# Pots.net
KiCad netlist of a schematic drawn in EAGLE
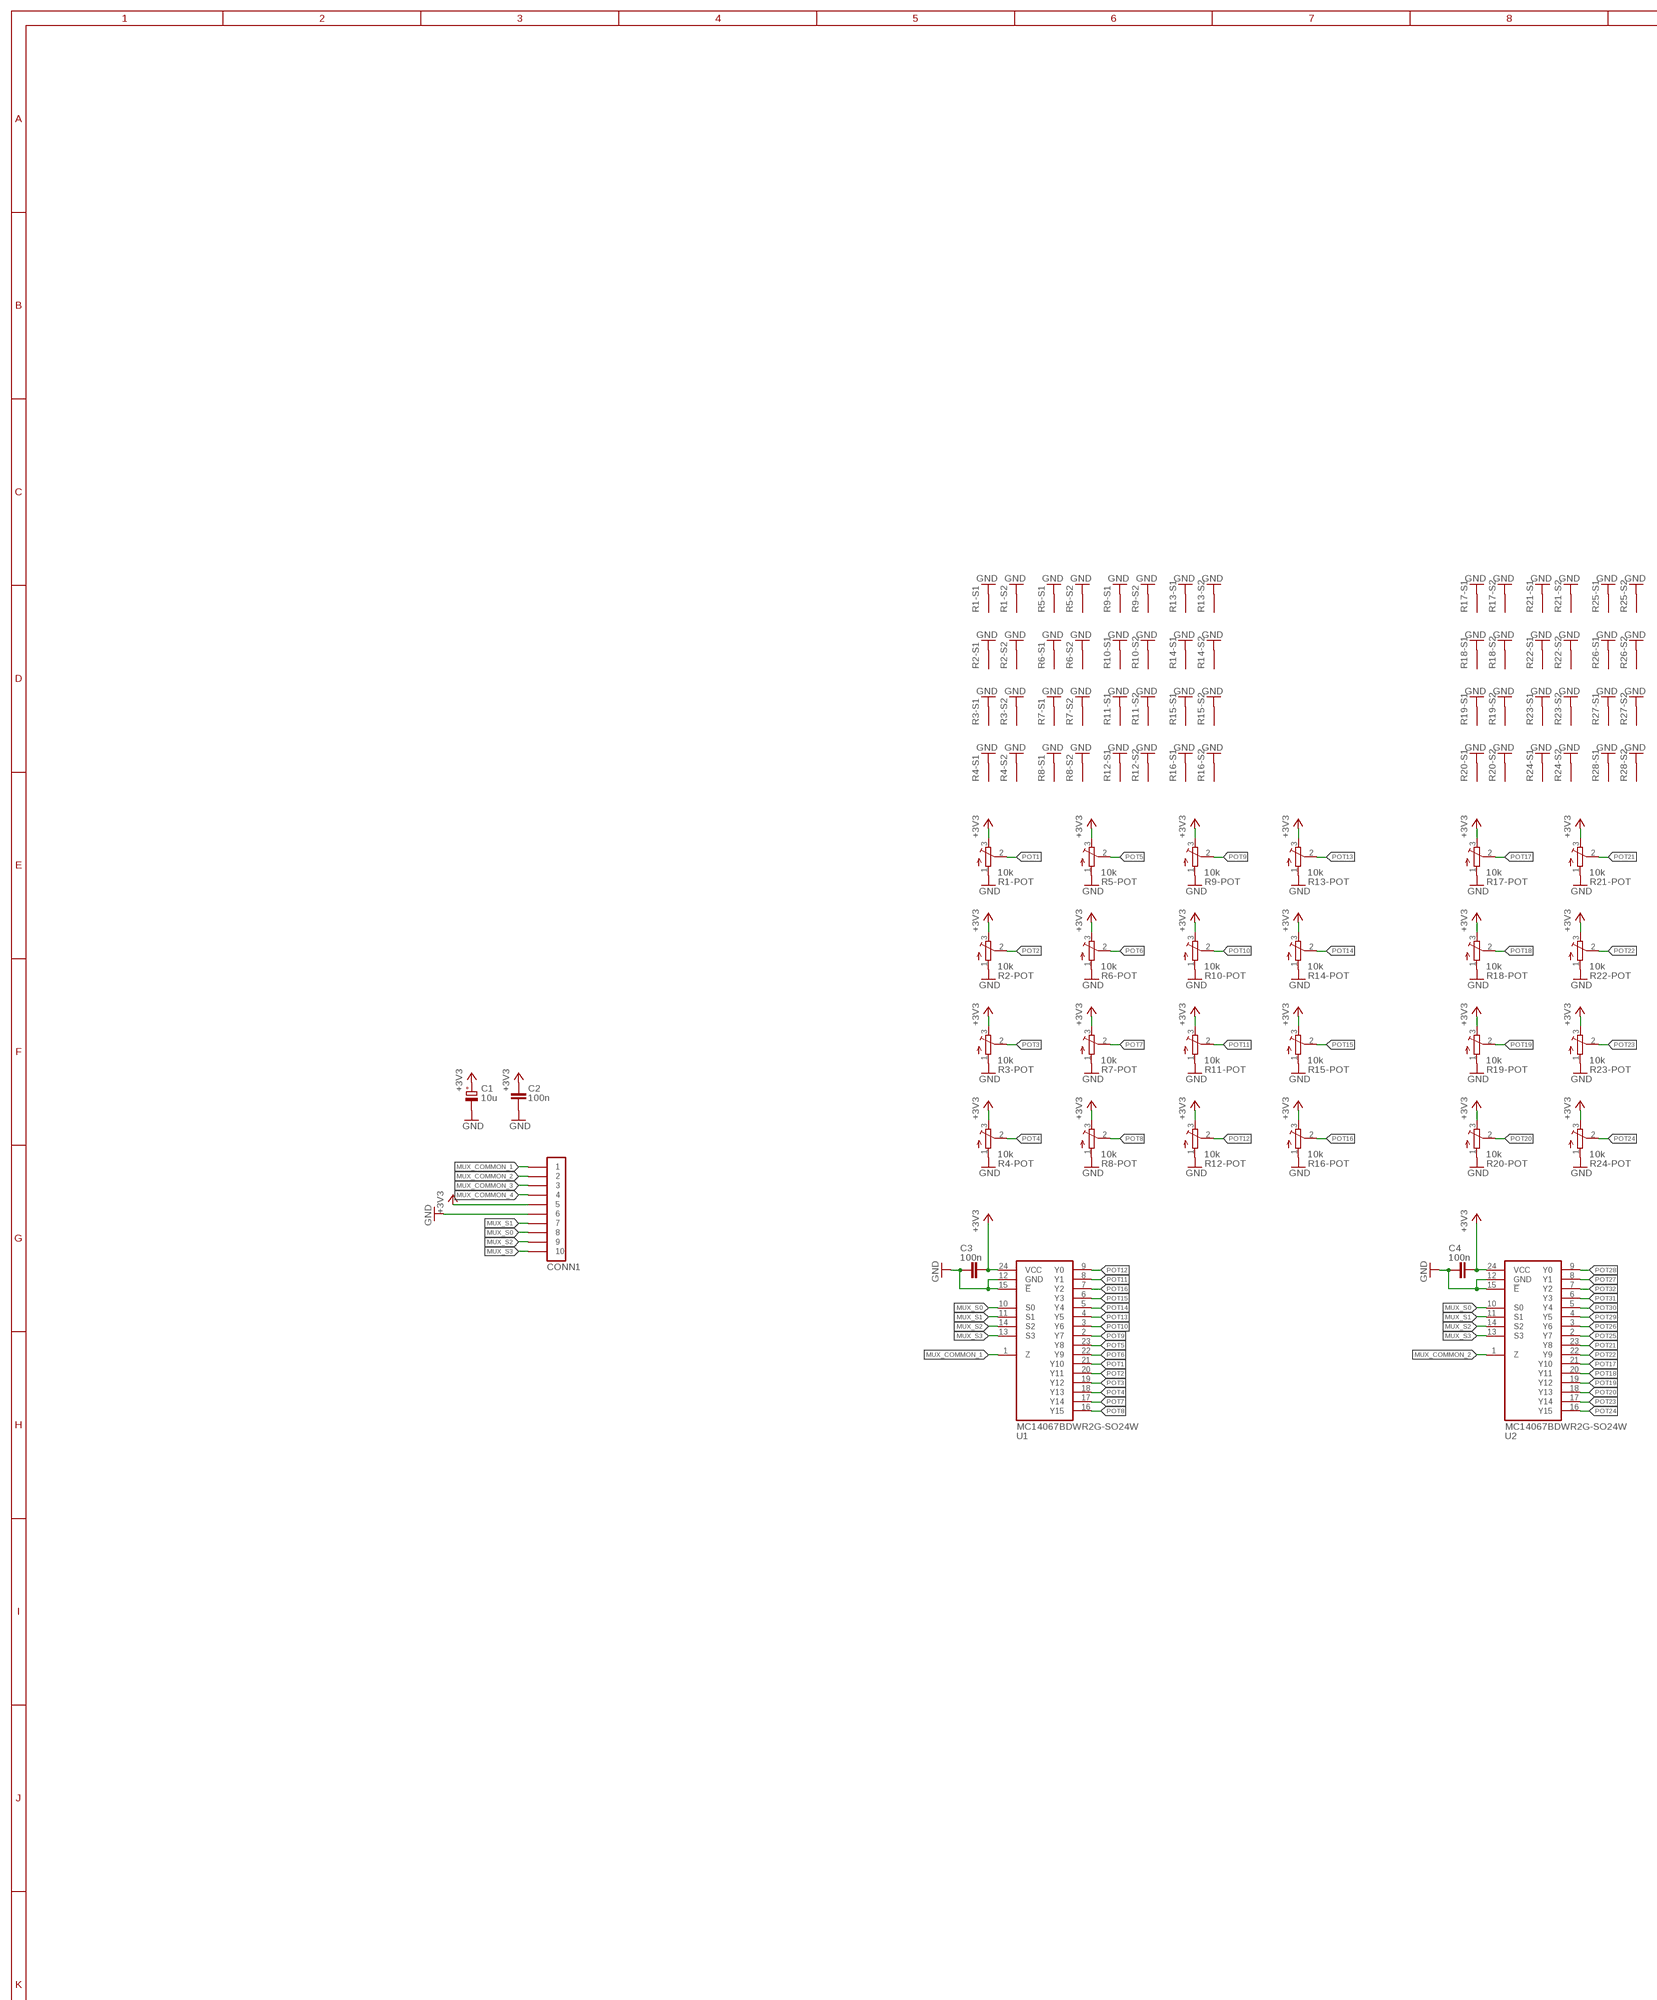
[diagram p0: schematic, sheet 1, part 1 of 3]
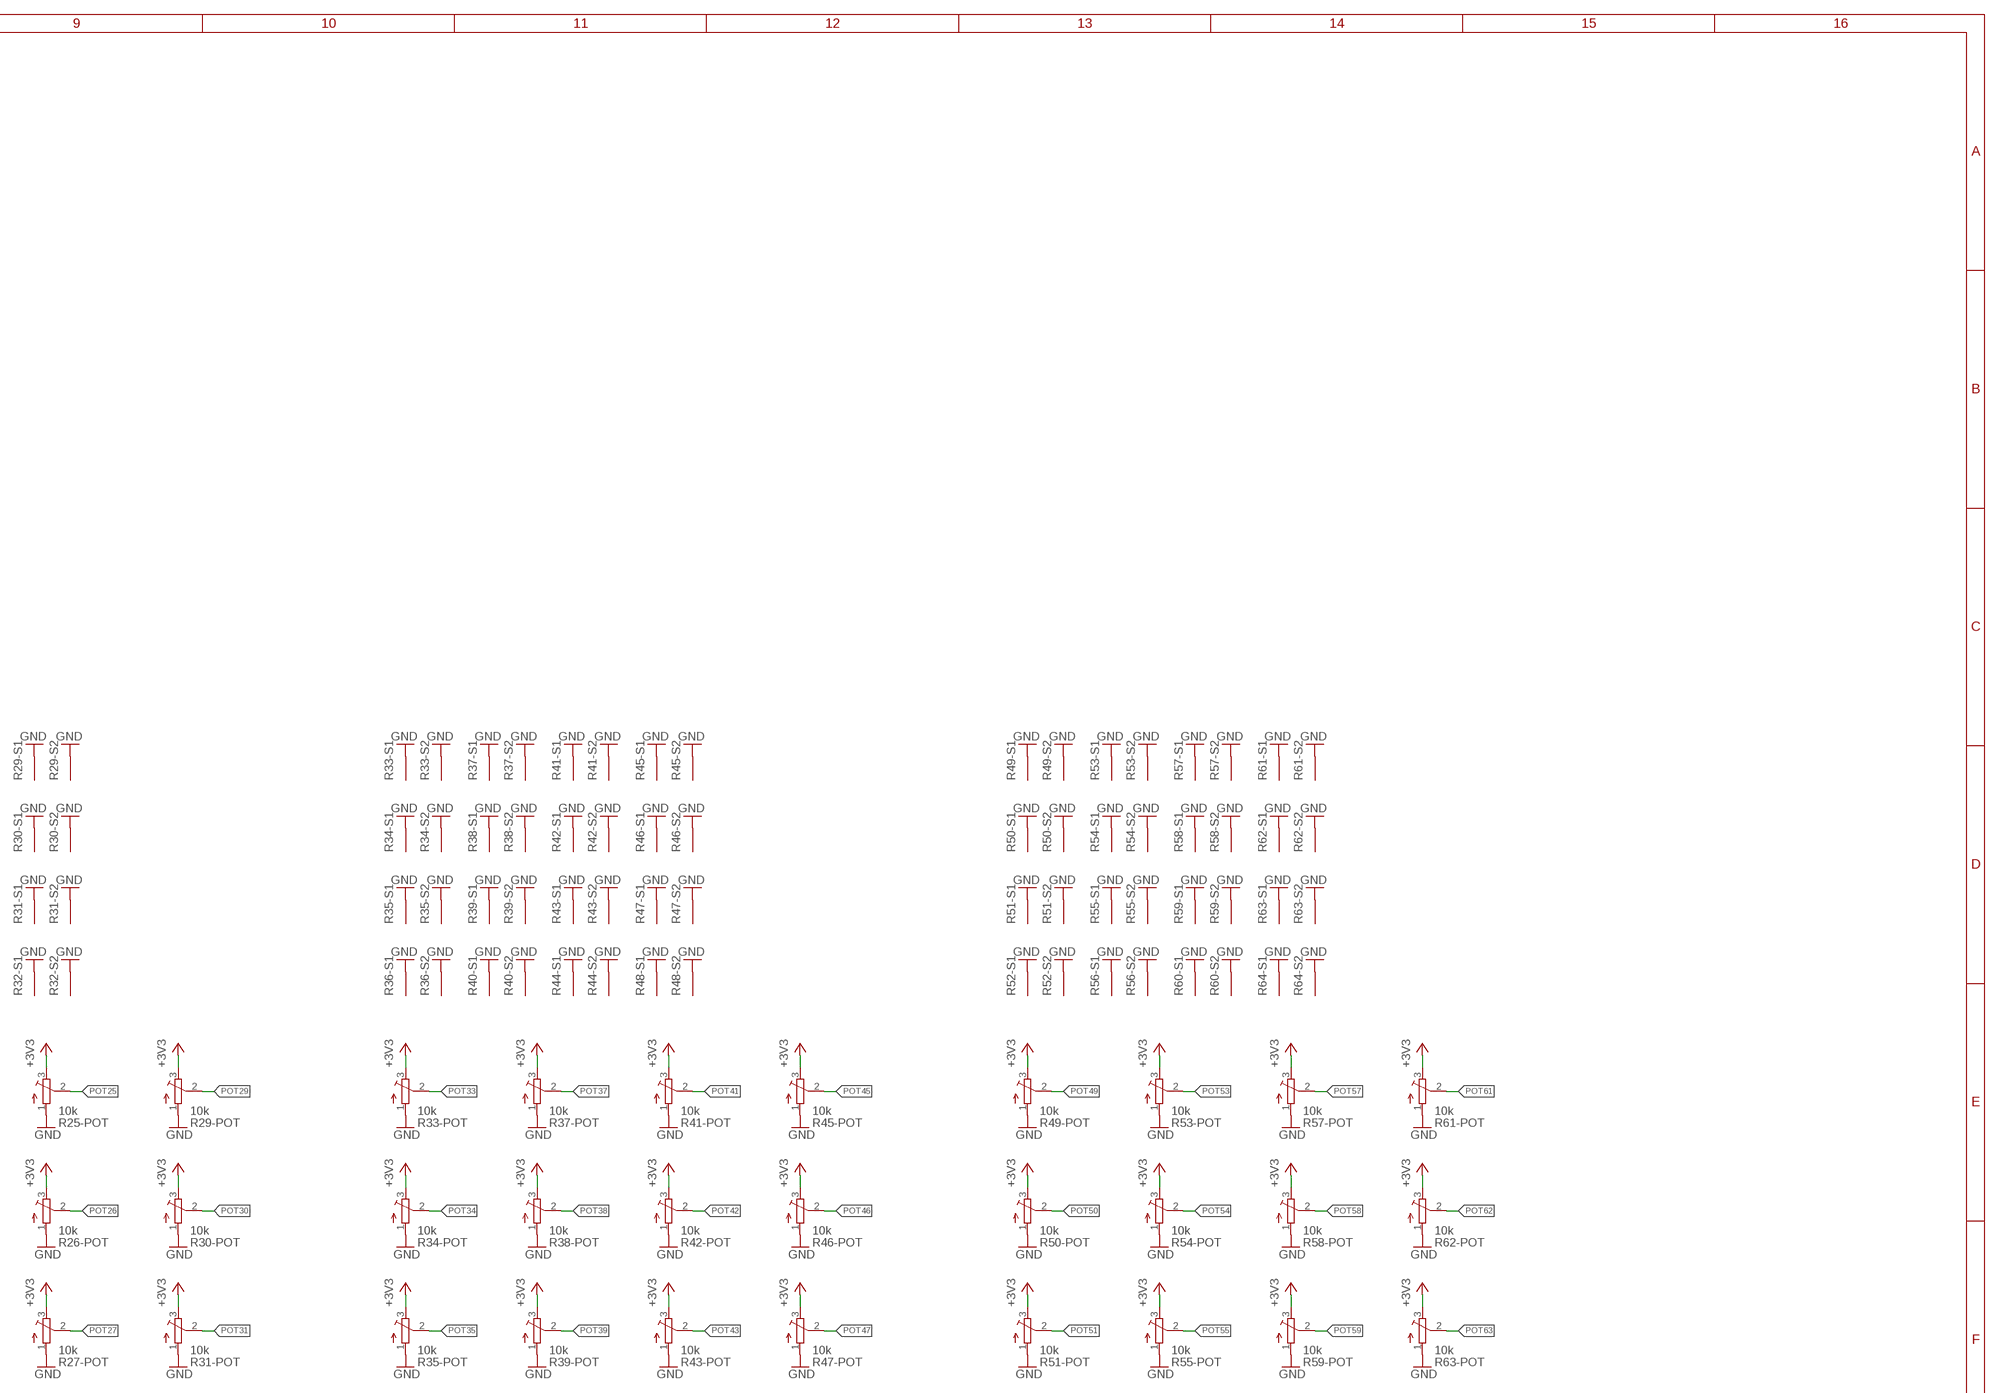
[diagram p1: schematic, sheet 1, part 2 of 3]
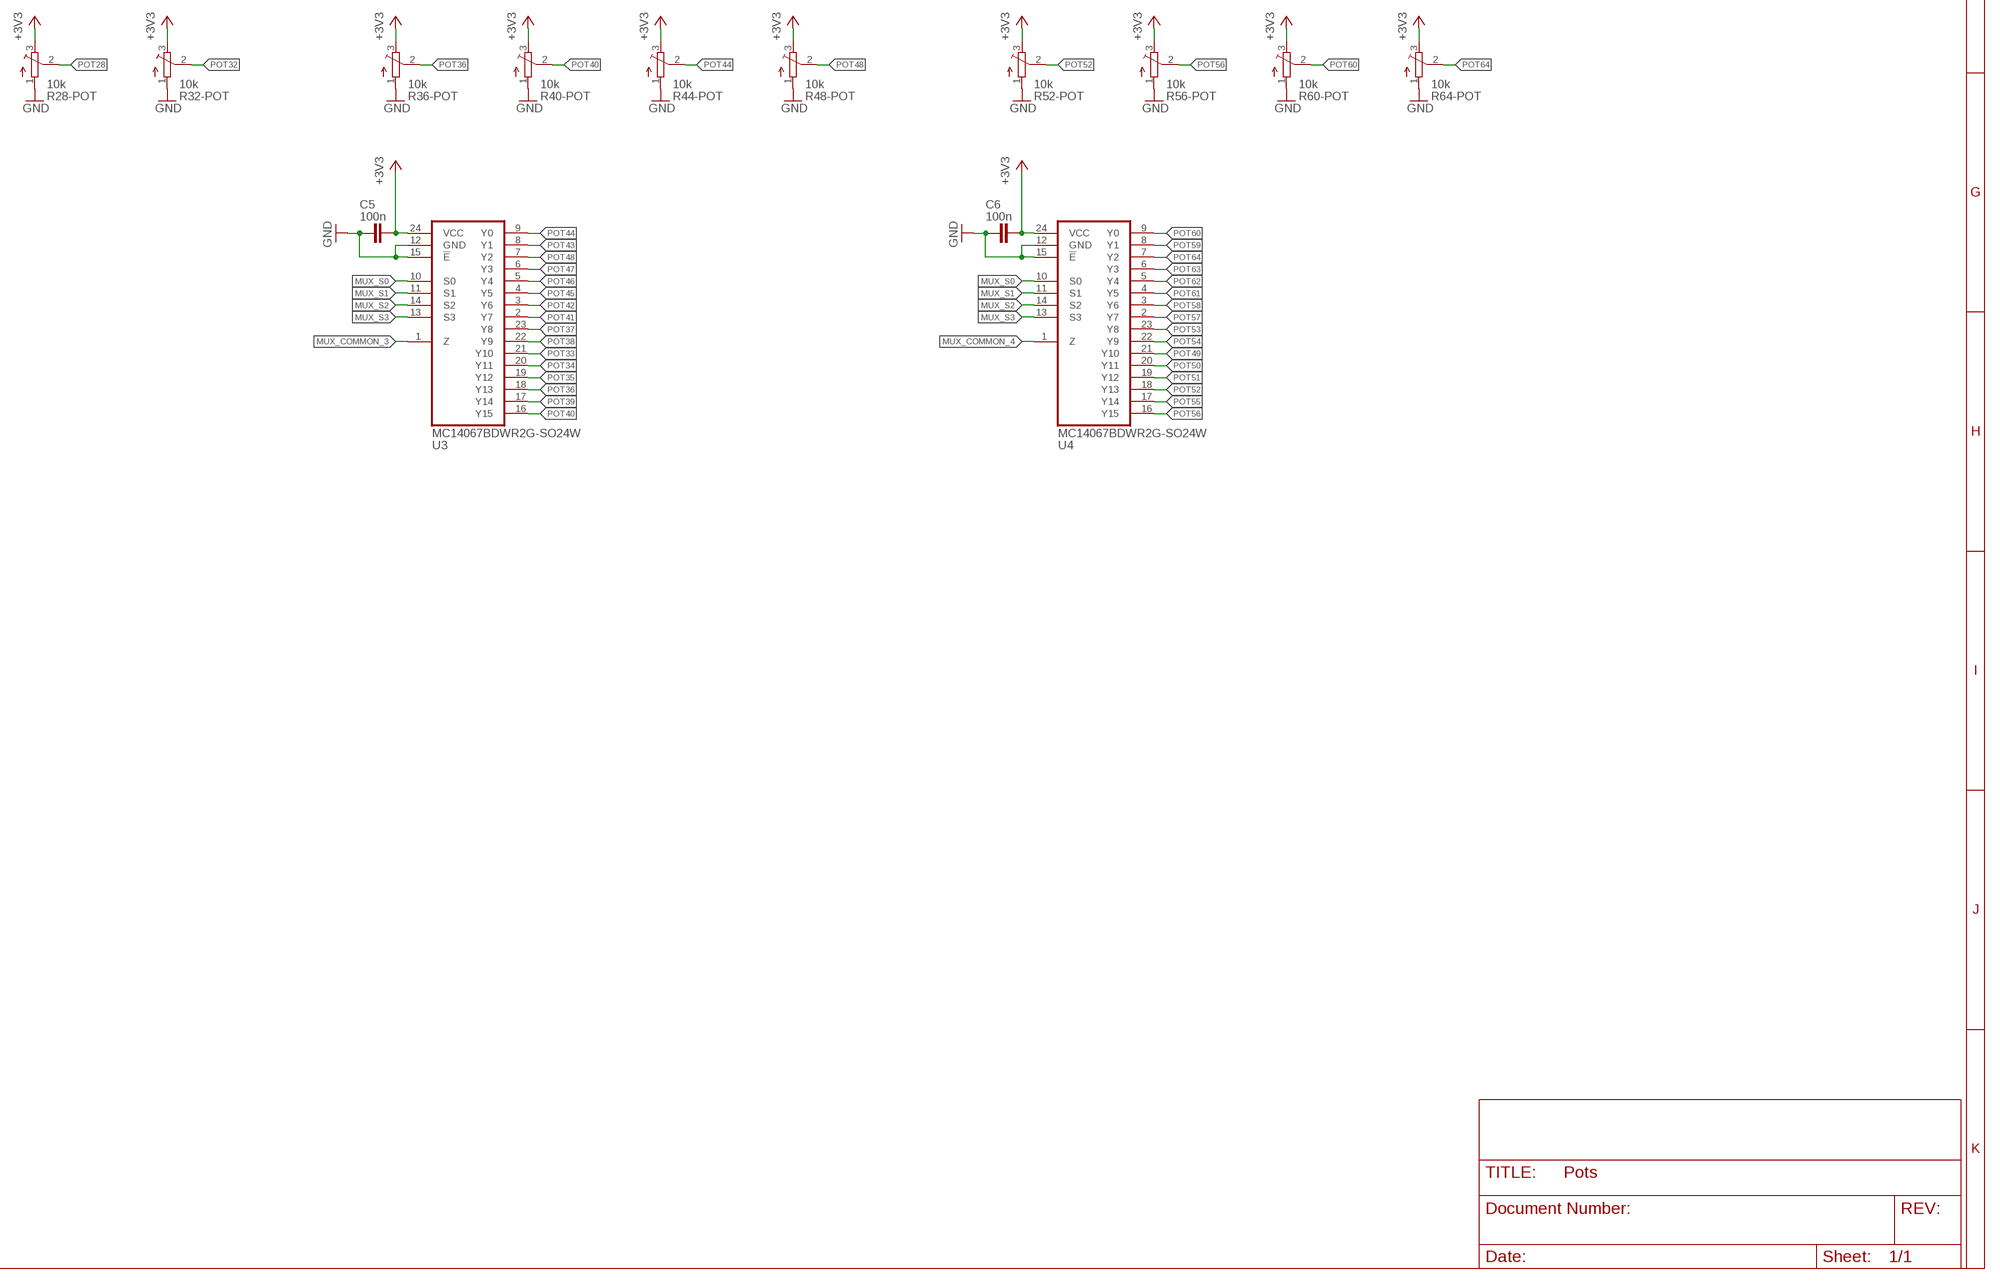
[diagram p2: schematic, sheet 1, part 3 of 3]

(export (version "E")
  (design (tool "Eeschema 10.0.6"))
  (components
    (comp (ref "C1")
      (value "10u")
      (footprint "eagle-import:C-TH-E-0401")
      (libsource (lib "eagle-import") (part "ELECTROLYTIC_CAPACITOR-C-TH-E-0401"))
    )
    (comp (ref "C2")
      (value "100n")
      (footprint "eagle-import:C0805")
      (libsource (lib "eagle-import") (part "CAPACITOR-0805"))
    )
    (comp (ref "C3")
      (value "100n")
      (footprint "eagle-import:C0805")
      (libsource (lib "eagle-import") (part "CAPACITOR-0805"))
    )
    (comp (ref "C4")
      (value "100n")
      (footprint "eagle-import:C0805")
      (libsource (lib "eagle-import") (part "CAPACITOR-0805"))
    )
    (comp (ref "C5")
      (value "100n")
      (footprint "eagle-import:C0805")
      (libsource (lib "eagle-import") (part "CAPACITOR-0805"))
    )
    (comp (ref "C6")
      (value "100n")
      (footprint "eagle-import:C0805")
      (libsource (lib "eagle-import") (part "CAPACITOR-0805"))
    )
    (comp (ref "CONN1")
      (value "PINHD-1X10-FFC-1MM-Z")
      (footprint "eagle-import:MOLEX-52271-1079")
      (fields (field (name "MANUFACTURER") "Molex") (field (name "MPN") "52271-1079"))
      (libsource (lib "eagle-import") (part "PINHD-1X10-FFC-1MM-Z"))
    )
    (comp (ref "R1")
      (value "10k")
      (footprint "eagle-import:PTV09A-4025F-B103")
      (libsource (lib "eagle-import") (part "PTV09A-4025F-B103"))
    )
    (comp (ref "R2")
      (value "10k")
      (footprint "eagle-import:PTV09A-4025F-B103")
      (libsource (lib "eagle-import") (part "PTV09A-4025F-B103"))
    )
    (comp (ref "R3")
      (value "10k")
      (footprint "eagle-import:PTV09A-4025F-B103")
      (libsource (lib "eagle-import") (part "PTV09A-4025F-B103"))
    )
    (comp (ref "R4")
      (value "10k")
      (footprint "eagle-import:PTV09A-4025F-B103")
      (libsource (lib "eagle-import") (part "PTV09A-4025F-B103"))
    )
    (comp (ref "R5")
      (value "10k")
      (footprint "eagle-import:PTV09A-4025F-B103")
      (libsource (lib "eagle-import") (part "PTV09A-4025F-B103"))
    )
    (comp (ref "R6")
      (value "10k")
      (footprint "eagle-import:PTV09A-4025F-B103")
      (libsource (lib "eagle-import") (part "PTV09A-4025F-B103"))
    )
    (comp (ref "R7")
      (value "10k")
      (footprint "eagle-import:PTV09A-4025F-B103")
      (libsource (lib "eagle-import") (part "PTV09A-4025F-B103"))
    )
    (comp (ref "R8")
      (value "10k")
      (footprint "eagle-import:PTV09A-4025F-B103")
      (libsource (lib "eagle-import") (part "PTV09A-4025F-B103"))
    )
    (comp (ref "R9")
      (value "10k")
      (footprint "eagle-import:PTV09A-4025F-B103")
      (libsource (lib "eagle-import") (part "PTV09A-4025F-B103"))
    )
    (comp (ref "R10")
      (value "10k")
      (footprint "eagle-import:PTV09A-4025F-B103")
      (libsource (lib "eagle-import") (part "PTV09A-4025F-B103"))
    )
    (comp (ref "R11")
      (value "10k")
      (footprint "eagle-import:PTV09A-4025F-B103")
      (libsource (lib "eagle-import") (part "PTV09A-4025F-B103"))
    )
    (comp (ref "R12")
      (value "10k")
      (footprint "eagle-import:PTV09A-4025F-B103")
      (libsource (lib "eagle-import") (part "PTV09A-4025F-B103"))
    )
    (comp (ref "R13")
      (value "10k")
      (footprint "eagle-import:PTV09A-4025F-B103")
      (libsource (lib "eagle-import") (part "PTV09A-4025F-B103"))
    )
    (comp (ref "R14")
      (value "10k")
      (footprint "eagle-import:PTV09A-4025F-B103")
      (libsource (lib "eagle-import") (part "PTV09A-4025F-B103"))
    )
    (comp (ref "R15")
      (value "10k")
      (footprint "eagle-import:PTV09A-4025F-B103")
      (libsource (lib "eagle-import") (part "PTV09A-4025F-B103"))
    )
    (comp (ref "R16")
      (value "10k")
      (footprint "eagle-import:PTV09A-4025F-B103")
      (libsource (lib "eagle-import") (part "PTV09A-4025F-B103"))
    )
    (comp (ref "R17")
      (value "10k")
      (footprint "eagle-import:PTV09A-4025F-B103")
      (libsource (lib "eagle-import") (part "PTV09A-4025F-B103"))
    )
    (comp (ref "R18")
      (value "10k")
      (footprint "eagle-import:PTV09A-4025F-B103")
      (libsource (lib "eagle-import") (part "PTV09A-4025F-B103"))
    )
    (comp (ref "R19")
      (value "10k")
      (footprint "eagle-import:PTV09A-4025F-B103")
      (libsource (lib "eagle-import") (part "PTV09A-4025F-B103"))
    )
    (comp (ref "R20")
      (value "10k")
      (footprint "eagle-import:PTV09A-4025F-B103")
      (libsource (lib "eagle-import") (part "PTV09A-4025F-B103"))
    )
    (comp (ref "R21")
      (value "10k")
      (footprint "eagle-import:PTV09A-4025F-B103")
      (libsource (lib "eagle-import") (part "PTV09A-4025F-B103"))
    )
    (comp (ref "R22")
      (value "10k")
      (footprint "eagle-import:PTV09A-4025F-B103")
      (libsource (lib "eagle-import") (part "PTV09A-4025F-B103"))
    )
    (comp (ref "R23")
      (value "10k")
      (footprint "eagle-import:PTV09A-4025F-B103")
      (libsource (lib "eagle-import") (part "PTV09A-4025F-B103"))
    )
    (comp (ref "R24")
      (value "10k")
      (footprint "eagle-import:PTV09A-4025F-B103")
      (libsource (lib "eagle-import") (part "PTV09A-4025F-B103"))
    )
    (comp (ref "R25")
      (value "10k")
      (footprint "eagle-import:PTV09A-4025F-B103")
      (libsource (lib "eagle-import") (part "PTV09A-4025F-B103"))
    )
    (comp (ref "R26")
      (value "10k")
      (footprint "eagle-import:PTV09A-4025F-B103")
      (libsource (lib "eagle-import") (part "PTV09A-4025F-B103"))
    )
    (comp (ref "R27")
      (value "10k")
      (footprint "eagle-import:PTV09A-4025F-B103")
      (libsource (lib "eagle-import") (part "PTV09A-4025F-B103"))
    )
    (comp (ref "R28")
      (value "10k")
      (footprint "eagle-import:PTV09A-4025F-B103")
      (libsource (lib "eagle-import") (part "PTV09A-4025F-B103"))
    )
    (comp (ref "R29")
      (value "10k")
      (footprint "eagle-import:PTV09A-4025F-B103")
      (libsource (lib "eagle-import") (part "PTV09A-4025F-B103"))
    )
    (comp (ref "R30")
      (value "10k")
      (footprint "eagle-import:PTV09A-4025F-B103")
      (libsource (lib "eagle-import") (part "PTV09A-4025F-B103"))
    )
    (comp (ref "R31")
      (value "10k")
      (footprint "eagle-import:PTV09A-4025F-B103")
      (libsource (lib "eagle-import") (part "PTV09A-4025F-B103"))
    )
    (comp (ref "R32")
      (value "10k")
      (footprint "eagle-import:PTV09A-4025F-B103")
      (libsource (lib "eagle-import") (part "PTV09A-4025F-B103"))
    )
    (comp (ref "R33")
      (value "10k")
      (footprint "eagle-import:PTV09A-4025F-B103")
      (libsource (lib "eagle-import") (part "PTV09A-4025F-B103"))
    )
    (comp (ref "R34")
      (value "10k")
      (footprint "eagle-import:PTV09A-4025F-B103")
      (libsource (lib "eagle-import") (part "PTV09A-4025F-B103"))
    )
    (comp (ref "R35")
      (value "10k")
      (footprint "eagle-import:PTV09A-4025F-B103")
      (libsource (lib "eagle-import") (part "PTV09A-4025F-B103"))
    )
    (comp (ref "R36")
      (value "10k")
      (footprint "eagle-import:PTV09A-4025F-B103")
      (libsource (lib "eagle-import") (part "PTV09A-4025F-B103"))
    )
    (comp (ref "R37")
      (value "10k")
      (footprint "eagle-import:PTV09A-4025F-B103")
      (libsource (lib "eagle-import") (part "PTV09A-4025F-B103"))
    )
    (comp (ref "R38")
      (value "10k")
      (footprint "eagle-import:PTV09A-4025F-B103")
      (libsource (lib "eagle-import") (part "PTV09A-4025F-B103"))
    )
    (comp (ref "R39")
      (value "10k")
      (footprint "eagle-import:PTV09A-4025F-B103")
      (libsource (lib "eagle-import") (part "PTV09A-4025F-B103"))
    )
    (comp (ref "R40")
      (value "10k")
      (footprint "eagle-import:PTV09A-4025F-B103")
      (libsource (lib "eagle-import") (part "PTV09A-4025F-B103"))
    )
    (comp (ref "R41")
      (value "10k")
      (footprint "eagle-import:PTV09A-4025F-B103")
      (libsource (lib "eagle-import") (part "PTV09A-4025F-B103"))
    )
    (comp (ref "R42")
      (value "10k")
      (footprint "eagle-import:PTV09A-4025F-B103")
      (libsource (lib "eagle-import") (part "PTV09A-4025F-B103"))
    )
    (comp (ref "R43")
      (value "10k")
      (footprint "eagle-import:PTV09A-4025F-B103")
      (libsource (lib "eagle-import") (part "PTV09A-4025F-B103"))
    )
    (comp (ref "R44")
      (value "10k")
      (footprint "eagle-import:PTV09A-4025F-B103")
      (libsource (lib "eagle-import") (part "PTV09A-4025F-B103"))
    )
    (comp (ref "R45")
      (value "10k")
      (footprint "eagle-import:PTV09A-4025F-B103")
      (libsource (lib "eagle-import") (part "PTV09A-4025F-B103"))
    )
    (comp (ref "R46")
      (value "10k")
      (footprint "eagle-import:PTV09A-4025F-B103")
      (libsource (lib "eagle-import") (part "PTV09A-4025F-B103"))
    )
    (comp (ref "R47")
      (value "10k")
      (footprint "eagle-import:PTV09A-4025F-B103")
      (libsource (lib "eagle-import") (part "PTV09A-4025F-B103"))
    )
    (comp (ref "R48")
      (value "10k")
      (footprint "eagle-import:PTV09A-4025F-B103")
      (libsource (lib "eagle-import") (part "PTV09A-4025F-B103"))
    )
    (comp (ref "R49")
      (value "10k")
      (footprint "eagle-import:PTV09A-4025F-B103")
      (libsource (lib "eagle-import") (part "PTV09A-4025F-B103"))
    )
    (comp (ref "R50")
      (value "10k")
      (footprint "eagle-import:PTV09A-4025F-B103")
      (libsource (lib "eagle-import") (part "PTV09A-4025F-B103"))
    )
    (comp (ref "R51")
      (value "10k")
      (footprint "eagle-import:PTV09A-4025F-B103")
      (libsource (lib "eagle-import") (part "PTV09A-4025F-B103"))
    )
    (comp (ref "R52")
      (value "10k")
      (footprint "eagle-import:PTV09A-4025F-B103")
      (libsource (lib "eagle-import") (part "PTV09A-4025F-B103"))
    )
    (comp (ref "R53")
      (value "10k")
      (footprint "eagle-import:PTV09A-4025F-B103")
      (libsource (lib "eagle-import") (part "PTV09A-4025F-B103"))
    )
    (comp (ref "R54")
      (value "10k")
      (footprint "eagle-import:PTV09A-4025F-B103")
      (libsource (lib "eagle-import") (part "PTV09A-4025F-B103"))
    )
    (comp (ref "R55")
      (value "10k")
      (footprint "eagle-import:PTV09A-4025F-B103")
      (libsource (lib "eagle-import") (part "PTV09A-4025F-B103"))
    )
    (comp (ref "R56")
      (value "10k")
      (footprint "eagle-import:PTV09A-4025F-B103")
      (libsource (lib "eagle-import") (part "PTV09A-4025F-B103"))
    )
    (comp (ref "R57")
      (value "10k")
      (footprint "eagle-import:PTV09A-4025F-B103")
      (libsource (lib "eagle-import") (part "PTV09A-4025F-B103"))
    )
    (comp (ref "R58")
      (value "10k")
      (footprint "eagle-import:PTV09A-4025F-B103")
      (libsource (lib "eagle-import") (part "PTV09A-4025F-B103"))
    )
    (comp (ref "R59")
      (value "10k")
      (footprint "eagle-import:PTV09A-4025F-B103")
      (libsource (lib "eagle-import") (part "PTV09A-4025F-B103"))
    )
    (comp (ref "R60")
      (value "10k")
      (footprint "eagle-import:PTV09A-4025F-B103")
      (libsource (lib "eagle-import") (part "PTV09A-4025F-B103"))
    )
    (comp (ref "R61")
      (value "10k")
      (footprint "eagle-import:PTV09A-4025F-B103")
      (libsource (lib "eagle-import") (part "PTV09A-4025F-B103"))
    )
    (comp (ref "R62")
      (value "10k")
      (footprint "eagle-import:PTV09A-4025F-B103")
      (libsource (lib "eagle-import") (part "PTV09A-4025F-B103"))
    )
    (comp (ref "R63")
      (value "10k")
      (footprint "eagle-import:PTV09A-4025F-B103")
      (libsource (lib "eagle-import") (part "PTV09A-4025F-B103"))
    )
    (comp (ref "R64")
      (value "10k")
      (footprint "eagle-import:PTV09A-4025F-B103")
      (libsource (lib "eagle-import") (part "PTV09A-4025F-B103"))
    )
    (comp (ref "U1")
      (value "MC14067BDWR2G-SO24W")
      (footprint "eagle-import:SO24-W")
      (fields (field (name "MANUFACTURER") "ON Semiconductor") (field (name "MPN") "MC14067BDWR2G"))
      (libsource (lib "eagle-import") (part "MC14067BDWR2G-SO24W"))
    )
    (comp (ref "U2")
      (value "MC14067BDWR2G-SO24W")
      (footprint "eagle-import:SO24-W")
      (fields (field (name "MANUFACTURER") "ON Semiconductor") (field (name "MPN") "MC14067BDWR2G"))
      (libsource (lib "eagle-import") (part "MC14067BDWR2G-SO24W"))
    )
    (comp (ref "U3")
      (value "MC14067BDWR2G-SO24W")
      (footprint "eagle-import:SO24-W")
      (fields (field (name "MANUFACTURER") "ON Semiconductor") (field (name "MPN") "MC14067BDWR2G"))
      (libsource (lib "eagle-import") (part "MC14067BDWR2G-SO24W"))
    )
    (comp (ref "U4")
      (value "MC14067BDWR2G-SO24W")
      (footprint "eagle-import:SO24-W")
      (fields (field (name "MANUFACTURER") "ON Semiconductor") (field (name "MPN") "MC14067BDWR2G"))
      (libsource (lib "eagle-import") (part "MC14067BDWR2G-SO24W"))
    )
  )
  (nets
    (net (code "1") (name "+3V3") (class "Default")
      (node (ref "C1") (pin "+") (pinfunction "+_+") (pintype "passive"))
      (node (ref "C2") (pin "1") (pinfunction "1_1") (pintype "passive"))
      (node (ref "C3") (pin "2") (pinfunction "2_2") (pintype "passive"))
      (node (ref "C4") (pin "2") (pinfunction "2_2") (pintype "passive"))
      (node (ref "C5") (pin "2") (pinfunction "2_2") (pintype "passive"))
      (node (ref "C6") (pin "2") (pinfunction "2_2") (pintype "passive"))
      (node (ref "CONN1") (pin "5") (pinfunction "5_5") (pintype "passive"))
      (node (ref "R1") (pin "3") (pinfunction "3_3") (pintype "passive"))
      (node (ref "R10") (pin "3") (pinfunction "3_3") (pintype "passive"))
      (node (ref "R11") (pin "3") (pinfunction "3_3") (pintype "passive"))
      (node (ref "R12") (pin "3") (pinfunction "3_3") (pintype "passive"))
      (node (ref "R13") (pin "3") (pinfunction "3_3") (pintype "passive"))
      (node (ref "R14") (pin "3") (pinfunction "3_3") (pintype "passive"))
      (node (ref "R15") (pin "3") (pinfunction "3_3") (pintype "passive"))
      (node (ref "R16") (pin "3") (pinfunction "3_3") (pintype "passive"))
      (node (ref "R17") (pin "3") (pinfunction "3_3") (pintype "passive"))
      (node (ref "R18") (pin "3") (pinfunction "3_3") (pintype "passive"))
      (node (ref "R19") (pin "3") (pinfunction "3_3") (pintype "passive"))
      (node (ref "R2") (pin "3") (pinfunction "3_3") (pintype "passive"))
      (node (ref "R20") (pin "3") (pinfunction "3_3") (pintype "passive"))
      (node (ref "R21") (pin "3") (pinfunction "3_3") (pintype "passive"))
      (node (ref "R22") (pin "3") (pinfunction "3_3") (pintype "passive"))
      (node (ref "R23") (pin "3") (pinfunction "3_3") (pintype "passive"))
      (node (ref "R24") (pin "3") (pinfunction "3_3") (pintype "passive"))
      (node (ref "R25") (pin "3") (pinfunction "3_3") (pintype "passive"))
      (node (ref "R26") (pin "3") (pinfunction "3_3") (pintype "passive"))
      (node (ref "R27") (pin "3") (pinfunction "3_3") (pintype "passive"))
      (node (ref "R28") (pin "3") (pinfunction "3_3") (pintype "passive"))
      (node (ref "R29") (pin "3") (pinfunction "3_3") (pintype "passive"))
      (node (ref "R3") (pin "3") (pinfunction "3_3") (pintype "passive"))
      (node (ref "R30") (pin "3") (pinfunction "3_3") (pintype "passive"))
      (node (ref "R31") (pin "3") (pinfunction "3_3") (pintype "passive"))
      (node (ref "R32") (pin "3") (pinfunction "3_3") (pintype "passive"))
      (node (ref "R33") (pin "3") (pinfunction "3_3") (pintype "passive"))
      (node (ref "R34") (pin "3") (pinfunction "3_3") (pintype "passive"))
      (node (ref "R35") (pin "3") (pinfunction "3_3") (pintype "passive"))
      (node (ref "R36") (pin "3") (pinfunction "3_3") (pintype "passive"))
      (node (ref "R37") (pin "3") (pinfunction "3_3") (pintype "passive"))
      (node (ref "R38") (pin "3") (pinfunction "3_3") (pintype "passive"))
      (node (ref "R39") (pin "3") (pinfunction "3_3") (pintype "passive"))
      (node (ref "R4") (pin "3") (pinfunction "3_3") (pintype "passive"))
      (node (ref "R40") (pin "3") (pinfunction "3_3") (pintype "passive"))
      (node (ref "R41") (pin "3") (pinfunction "3_3") (pintype "passive"))
      (node (ref "R42") (pin "3") (pinfunction "3_3") (pintype "passive"))
      (node (ref "R43") (pin "3") (pinfunction "3_3") (pintype "passive"))
      (node (ref "R44") (pin "3") (pinfunction "3_3") (pintype "passive"))
      (node (ref "R45") (pin "3") (pinfunction "3_3") (pintype "passive"))
      (node (ref "R46") (pin "3") (pinfunction "3_3") (pintype "passive"))
      (node (ref "R47") (pin "3") (pinfunction "3_3") (pintype "passive"))
      (node (ref "R48") (pin "3") (pinfunction "3_3") (pintype "passive"))
      (node (ref "R49") (pin "3") (pinfunction "3_3") (pintype "passive"))
      (node (ref "R5") (pin "3") (pinfunction "3_3") (pintype "passive"))
      (node (ref "R50") (pin "3") (pinfunction "3_3") (pintype "passive"))
      (node (ref "R51") (pin "3") (pinfunction "3_3") (pintype "passive"))
      (node (ref "R52") (pin "3") (pinfunction "3_3") (pintype "passive"))
      (node (ref "R53") (pin "3") (pinfunction "3_3") (pintype "passive"))
      (node (ref "R54") (pin "3") (pinfunction "3_3") (pintype "passive"))
      (node (ref "R55") (pin "3") (pinfunction "3_3") (pintype "passive"))
      (node (ref "R56") (pin "3") (pinfunction "3_3") (pintype "passive"))
      (node (ref "R57") (pin "3") (pinfunction "3_3") (pintype "passive"))
      (node (ref "R58") (pin "3") (pinfunction "3_3") (pintype "passive"))
      (node (ref "R59") (pin "3") (pinfunction "3_3") (pintype "passive"))
      (node (ref "R6") (pin "3") (pinfunction "3_3") (pintype "passive"))
      (node (ref "R60") (pin "3") (pinfunction "3_3") (pintype "passive"))
      (node (ref "R61") (pin "3") (pinfunction "3_3") (pintype "passive"))
      (node (ref "R62") (pin "3") (pinfunction "3_3") (pintype "passive"))
      (node (ref "R63") (pin "3") (pinfunction "3_3") (pintype "passive"))
      (node (ref "R64") (pin "3") (pinfunction "3_3") (pintype "passive"))
      (node (ref "R7") (pin "3") (pinfunction "3_3") (pintype "passive"))
      (node (ref "R8") (pin "3") (pinfunction "3_3") (pintype "passive"))
      (node (ref "R9") (pin "3") (pinfunction "3_3") (pintype "passive"))
      (node (ref "U1") (pin "24") (pinfunction "VCC_24") (pintype "passive"))
      (node (ref "U2") (pin "24") (pinfunction "VCC_24") (pintype "passive"))
      (node (ref "U3") (pin "24") (pinfunction "VCC_24") (pintype "passive"))
      (node (ref "U4") (pin "24") (pinfunction "VCC_24") (pintype "passive"))
    )
    (net (code "2") (name "GND") (class "Default")
      (node (ref "C1") (pin "-") (pinfunction "-_-") (pintype "passive"))
      (node (ref "C2") (pin "2") (pinfunction "2_2") (pintype "passive"))
      (node (ref "C3") (pin "1") (pinfunction "1_1") (pintype "passive"))
      (node (ref "C4") (pin "1") (pinfunction "1_1") (pintype "passive"))
      (node (ref "C5") (pin "1") (pinfunction "1_1") (pintype "passive"))
      (node (ref "C6") (pin "1") (pinfunction "1_1") (pintype "passive"))
      (node (ref "CONN1") (pin "6") (pinfunction "6_6") (pintype "passive"))
      (node (ref "R1") (pin "1") (pinfunction "1_1") (pintype "passive"))
      (node (ref "R1") (pin "S1") (pinfunction "S_S1") (pintype "passive"))
      (node (ref "R1") (pin "S2") (pinfunction "S_S2") (pintype "passive"))
      (node (ref "R10") (pin "1") (pinfunction "1_1") (pintype "passive"))
      (node (ref "R10") (pin "S1") (pinfunction "S_S1") (pintype "passive"))
      (node (ref "R10") (pin "S2") (pinfunction "S_S2") (pintype "passive"))
      (node (ref "R11") (pin "1") (pinfunction "1_1") (pintype "passive"))
      (node (ref "R11") (pin "S1") (pinfunction "S_S1") (pintype "passive"))
      (node (ref "R11") (pin "S2") (pinfunction "S_S2") (pintype "passive"))
      (node (ref "R12") (pin "1") (pinfunction "1_1") (pintype "passive"))
      (node (ref "R12") (pin "S1") (pinfunction "S_S1") (pintype "passive"))
      (node (ref "R12") (pin "S2") (pinfunction "S_S2") (pintype "passive"))
      (node (ref "R13") (pin "1") (pinfunction "1_1") (pintype "passive"))
      (node (ref "R13") (pin "S1") (pinfunction "S_S1") (pintype "passive"))
      (node (ref "R13") (pin "S2") (pinfunction "S_S2") (pintype "passive"))
      (node (ref "R14") (pin "1") (pinfunction "1_1") (pintype "passive"))
      (node (ref "R14") (pin "S1") (pinfunction "S_S1") (pintype "passive"))
      (node (ref "R14") (pin "S2") (pinfunction "S_S2") (pintype "passive"))
      (node (ref "R15") (pin "1") (pinfunction "1_1") (pintype "passive"))
      (node (ref "R15") (pin "S1") (pinfunction "S_S1") (pintype "passive"))
      (node (ref "R15") (pin "S2") (pinfunction "S_S2") (pintype "passive"))
      (node (ref "R16") (pin "1") (pinfunction "1_1") (pintype "passive"))
      (node (ref "R16") (pin "S1") (pinfunction "S_S1") (pintype "passive"))
      (node (ref "R16") (pin "S2") (pinfunction "S_S2") (pintype "passive"))
      (node (ref "R17") (pin "1") (pinfunction "1_1") (pintype "passive"))
      (node (ref "R17") (pin "S1") (pinfunction "S_S1") (pintype "passive"))
      (node (ref "R17") (pin "S2") (pinfunction "S_S2") (pintype "passive"))
      (node (ref "R18") (pin "1") (pinfunction "1_1") (pintype "passive"))
      (node (ref "R18") (pin "S1") (pinfunction "S_S1") (pintype "passive"))
      (node (ref "R18") (pin "S2") (pinfunction "S_S2") (pintype "passive"))
      (node (ref "R19") (pin "1") (pinfunction "1_1") (pintype "passive"))
      (node (ref "R19") (pin "S1") (pinfunction "S_S1") (pintype "passive"))
      (node (ref "R19") (pin "S2") (pinfunction "S_S2") (pintype "passive"))
      (node (ref "R2") (pin "1") (pinfunction "1_1") (pintype "passive"))
      (node (ref "R2") (pin "S1") (pinfunction "S_S1") (pintype "passive"))
      (node (ref "R2") (pin "S2") (pinfunction "S_S2") (pintype "passive"))
      (node (ref "R20") (pin "1") (pinfunction "1_1") (pintype "passive"))
      (node (ref "R20") (pin "S1") (pinfunction "S_S1") (pintype "passive"))
      (node (ref "R20") (pin "S2") (pinfunction "S_S2") (pintype "passive"))
      (node (ref "R21") (pin "1") (pinfunction "1_1") (pintype "passive"))
      (node (ref "R21") (pin "S1") (pinfunction "S_S1") (pintype "passive"))
      (node (ref "R21") (pin "S2") (pinfunction "S_S2") (pintype "passive"))
      (node (ref "R22") (pin "1") (pinfunction "1_1") (pintype "passive"))
      (node (ref "R22") (pin "S1") (pinfunction "S_S1") (pintype "passive"))
      (node (ref "R22") (pin "S2") (pinfunction "S_S2") (pintype "passive"))
      (node (ref "R23") (pin "1") (pinfunction "1_1") (pintype "passive"))
      (node (ref "R23") (pin "S1") (pinfunction "S_S1") (pintype "passive"))
      (node (ref "R23") (pin "S2") (pinfunction "S_S2") (pintype "passive"))
      (node (ref "R24") (pin "1") (pinfunction "1_1") (pintype "passive"))
      (node (ref "R24") (pin "S1") (pinfunction "S_S1") (pintype "passive"))
      (node (ref "R24") (pin "S2") (pinfunction "S_S2") (pintype "passive"))
      (node (ref "R25") (pin "1") (pinfunction "1_1") (pintype "passive"))
      (node (ref "R25") (pin "S1") (pinfunction "S_S1") (pintype "passive"))
      (node (ref "R25") (pin "S2") (pinfunction "S_S2") (pintype "passive"))
      (node (ref "R26") (pin "1") (pinfunction "1_1") (pintype "passive"))
      (node (ref "R26") (pin "S1") (pinfunction "S_S1") (pintype "passive"))
      (node (ref "R26") (pin "S2") (pinfunction "S_S2") (pintype "passive"))
      (node (ref "R27") (pin "1") (pinfunction "1_1") (pintype "passive"))
      (node (ref "R27") (pin "S1") (pinfunction "S_S1") (pintype "passive"))
      (node (ref "R27") (pin "S2") (pinfunction "S_S2") (pintype "passive"))
      (node (ref "R28") (pin "1") (pinfunction "1_1") (pintype "passive"))
      (node (ref "R28") (pin "S1") (pinfunction "S_S1") (pintype "passive"))
      (node (ref "R28") (pin "S2") (pinfunction "S_S2") (pintype "passive"))
      (node (ref "R29") (pin "1") (pinfunction "1_1") (pintype "passive"))
      (node (ref "R29") (pin "S1") (pinfunction "S_S1") (pintype "passive"))
      (node (ref "R29") (pin "S2") (pinfunction "S_S2") (pintype "passive"))
      (node (ref "R3") (pin "1") (pinfunction "1_1") (pintype "passive"))
      (node (ref "R3") (pin "S1") (pinfunction "S_S1") (pintype "passive"))
      (node (ref "R3") (pin "S2") (pinfunction "S_S2") (pintype "passive"))
      (node (ref "R30") (pin "1") (pinfunction "1_1") (pintype "passive"))
      (node (ref "R30") (pin "S1") (pinfunction "S_S1") (pintype "passive"))
      (node (ref "R30") (pin "S2") (pinfunction "S_S2") (pintype "passive"))
      (node (ref "R31") (pin "1") (pinfunction "1_1") (pintype "passive"))
      (node (ref "R31") (pin "S1") (pinfunction "S_S1") (pintype "passive"))
      (node (ref "R31") (pin "S2") (pinfunction "S_S2") (pintype "passive"))
      (node (ref "R32") (pin "1") (pinfunction "1_1") (pintype "passive"))
      (node (ref "R32") (pin "S1") (pinfunction "S_S1") (pintype "passive"))
      (node (ref "R32") (pin "S2") (pinfunction "S_S2") (pintype "passive"))
      (node (ref "R33") (pin "1") (pinfunction "1_1") (pintype "passive"))
      (node (ref "R33") (pin "S1") (pinfunction "S_S1") (pintype "passive"))
      (node (ref "R33") (pin "S2") (pinfunction "S_S2") (pintype "passive"))
      (node (ref "R34") (pin "1") (pinfunction "1_1") (pintype "passive"))
      (node (ref "R34") (pin "S1") (pinfunction "S_S1") (pintype "passive"))
      (node (ref "R34") (pin "S2") (pinfunction "S_S2") (pintype "passive"))
      (node (ref "R35") (pin "1") (pinfunction "1_1") (pintype "passive"))
      (node (ref "R35") (pin "S1") (pinfunction "S_S1") (pintype "passive"))
      (node (ref "R35") (pin "S2") (pinfunction "S_S2") (pintype "passive"))
      (node (ref "R36") (pin "1") (pinfunction "1_1") (pintype "passive"))
      (node (ref "R36") (pin "S1") (pinfunction "S_S1") (pintype "passive"))
      (node (ref "R36") (pin "S2") (pinfunction "S_S2") (pintype "passive"))
      (node (ref "R37") (pin "1") (pinfunction "1_1") (pintype "passive"))
      (node (ref "R37") (pin "S1") (pinfunction "S_S1") (pintype "passive"))
      (node (ref "R37") (pin "S2") (pinfunction "S_S2") (pintype "passive"))
      (node (ref "R38") (pin "1") (pinfunction "1_1") (pintype "passive"))
      (node (ref "R38") (pin "S1") (pinfunction "S_S1") (pintype "passive"))
      (node (ref "R38") (pin "S2") (pinfunction "S_S2") (pintype "passive"))
      (node (ref "R39") (pin "1") (pinfunction "1_1") (pintype "passive"))
      (node (ref "R39") (pin "S1") (pinfunction "S_S1") (pintype "passive"))
      (node (ref "R39") (pin "S2") (pinfunction "S_S2") (pintype "passive"))
      (node (ref "R4") (pin "1") (pinfunction "1_1") (pintype "passive"))
      (node (ref "R4") (pin "S1") (pinfunction "S_S1") (pintype "passive"))
      (node (ref "R4") (pin "S2") (pinfunction "S_S2") (pintype "passive"))
      (node (ref "R40") (pin "1") (pinfunction "1_1") (pintype "passive"))
      (node (ref "R40") (pin "S1") (pinfunction "S_S1") (pintype "passive"))
      (node (ref "R40") (pin "S2") (pinfunction "S_S2") (pintype "passive"))
      (node (ref "R41") (pin "1") (pinfunction "1_1") (pintype "passive"))
      (node (ref "R41") (pin "S1") (pinfunction "S_S1") (pintype "passive"))
      (node (ref "R41") (pin "S2") (pinfunction "S_S2") (pintype "passive"))
      (node (ref "R42") (pin "1") (pinfunction "1_1") (pintype "passive"))
      (node (ref "R42") (pin "S1") (pinfunction "S_S1") (pintype "passive"))
      (node (ref "R42") (pin "S2") (pinfunction "S_S2") (pintype "passive"))
      (node (ref "R43") (pin "1") (pinfunction "1_1") (pintype "passive"))
      (node (ref "R43") (pin "S1") (pinfunction "S_S1") (pintype "passive"))
      (node (ref "R43") (pin "S2") (pinfunction "S_S2") (pintype "passive"))
      (node (ref "R44") (pin "1") (pinfunction "1_1") (pintype "passive"))
      (node (ref "R44") (pin "S1") (pinfunction "S_S1") (pintype "passive"))
      (node (ref "R44") (pin "S2") (pinfunction "S_S2") (pintype "passive"))
      (node (ref "R45") (pin "1") (pinfunction "1_1") (pintype "passive"))
      (node (ref "R45") (pin "S1") (pinfunction "S_S1") (pintype "passive"))
      (node (ref "R45") (pin "S2") (pinfunction "S_S2") (pintype "passive"))
      (node (ref "R46") (pin "1") (pinfunction "1_1") (pintype "passive"))
      (node (ref "R46") (pin "S1") (pinfunction "S_S1") (pintype "passive"))
      (node (ref "R46") (pin "S2") (pinfunction "S_S2") (pintype "passive"))
      (node (ref "R47") (pin "1") (pinfunction "1_1") (pintype "passive"))
      (node (ref "R47") (pin "S1") (pinfunction "S_S1") (pintype "passive"))
      (node (ref "R47") (pin "S2") (pinfunction "S_S2") (pintype "passive"))
      (node (ref "R48") (pin "1") (pinfunction "1_1") (pintype "passive"))
      (node (ref "R48") (pin "S1") (pinfunction "S_S1") (pintype "passive"))
      (node (ref "R48") (pin "S2") (pinfunction "S_S2") (pintype "passive"))
      (node (ref "R49") (pin "1") (pinfunction "1_1") (pintype "passive"))
      (node (ref "R49") (pin "S1") (pinfunction "S_S1") (pintype "passive"))
      (node (ref "R49") (pin "S2") (pinfunction "S_S2") (pintype "passive"))
      (node (ref "R5") (pin "1") (pinfunction "1_1") (pintype "passive"))
      (node (ref "R5") (pin "S1") (pinfunction "S_S1") (pintype "passive"))
      (node (ref "R5") (pin "S2") (pinfunction "S_S2") (pintype "passive"))
      (node (ref "R50") (pin "1") (pinfunction "1_1") (pintype "passive"))
      (node (ref "R50") (pin "S1") (pinfunction "S_S1") (pintype "passive"))
      (node (ref "R50") (pin "S2") (pinfunction "S_S2") (pintype "passive"))
      (node (ref "R51") (pin "1") (pinfunction "1_1") (pintype "passive"))
      (node (ref "R51") (pin "S1") (pinfunction "S_S1") (pintype "passive"))
      (node (ref "R51") (pin "S2") (pinfunction "S_S2") (pintype "passive"))
      (node (ref "R52") (pin "1") (pinfunction "1_1") (pintype "passive"))
      (node (ref "R52") (pin "S1") (pinfunction "S_S1") (pintype "passive"))
      (node (ref "R52") (pin "S2") (pinfunction "S_S2") (pintype "passive"))
      (node (ref "R53") (pin "1") (pinfunction "1_1") (pintype "passive"))
      (node (ref "R53") (pin "S1") (pinfunction "S_S1") (pintype "passive"))
      (node (ref "R53") (pin "S2") (pinfunction "S_S2") (pintype "passive"))
      (node (ref "R54") (pin "1") (pinfunction "1_1") (pintype "passive"))
      (node (ref "R54") (pin "S1") (pinfunction "S_S1") (pintype "passive"))
      (node (ref "R54") (pin "S2") (pinfunction "S_S2") (pintype "passive"))
      (node (ref "R55") (pin "1") (pinfunction "1_1") (pintype "passive"))
      (node (ref "R55") (pin "S1") (pinfunction "S_S1") (pintype "passive"))
      (node (ref "R55") (pin "S2") (pinfunction "S_S2") (pintype "passive"))
      (node (ref "R56") (pin "1") (pinfunction "1_1") (pintype "passive"))
      (node (ref "R56") (pin "S1") (pinfunction "S_S1") (pintype "passive"))
      (node (ref "R56") (pin "S2") (pinfunction "S_S2") (pintype "passive"))
      (node (ref "R57") (pin "1") (pinfunction "1_1") (pintype "passive"))
      (node (ref "R57") (pin "S1") (pinfunction "S_S1") (pintype "passive"))
      (node (ref "R57") (pin "S2") (pinfunction "S_S2") (pintype "passive"))
      (node (ref "R58") (pin "1") (pinfunction "1_1") (pintype "passive"))
      (node (ref "R58") (pin "S1") (pinfunction "S_S1") (pintype "passive"))
      (node (ref "R58") (pin "S2") (pinfunction "S_S2") (pintype "passive"))
      (node (ref "R59") (pin "1") (pinfunction "1_1") (pintype "passive"))
      (node (ref "R59") (pin "S1") (pinfunction "S_S1") (pintype "passive"))
      (node (ref "R59") (pin "S2") (pinfunction "S_S2") (pintype "passive"))
      (node (ref "R6") (pin "1") (pinfunction "1_1") (pintype "passive"))
      (node (ref "R6") (pin "S1") (pinfunction "S_S1") (pintype "passive"))
      (node (ref "R6") (pin "S2") (pinfunction "S_S2") (pintype "passive"))
      (node (ref "R60") (pin "1") (pinfunction "1_1") (pintype "passive"))
      (node (ref "R60") (pin "S1") (pinfunction "S_S1") (pintype "passive"))
      (node (ref "R60") (pin "S2") (pinfunction "S_S2") (pintype "passive"))
      (node (ref "R61") (pin "1") (pinfunction "1_1") (pintype "passive"))
      (node (ref "R61") (pin "S1") (pinfunction "S_S1") (pintype "passive"))
      (node (ref "R61") (pin "S2") (pinfunction "S_S2") (pintype "passive"))
      (node (ref "R62") (pin "1") (pinfunction "1_1") (pintype "passive"))
      (node (ref "R62") (pin "S1") (pinfunction "S_S1") (pintype "passive"))
      (node (ref "R62") (pin "S2") (pinfunction "S_S2") (pintype "passive"))
      (node (ref "R63") (pin "1") (pinfunction "1_1") (pintype "passive"))
      (node (ref "R63") (pin "S1") (pinfunction "S_S1") (pintype "passive"))
      (node (ref "R63") (pin "S2") (pinfunction "S_S2") (pintype "passive"))
      (node (ref "R64") (pin "1") (pinfunction "1_1") (pintype "passive"))
      (node (ref "R64") (pin "S1") (pinfunction "S_S1") (pintype "passive"))
      (node (ref "R64") (pin "S2") (pinfunction "S_S2") (pintype "passive"))
      (node (ref "R7") (pin "1") (pinfunction "1_1") (pintype "passive"))
      (node (ref "R7") (pin "S1") (pinfunction "S_S1") (pintype "passive"))
      (node (ref "R7") (pin "S2") (pinfunction "S_S2") (pintype "passive"))
      (node (ref "R8") (pin "1") (pinfunction "1_1") (pintype "passive"))
      (node (ref "R8") (pin "S1") (pinfunction "S_S1") (pintype "passive"))
      (node (ref "R8") (pin "S2") (pinfunction "S_S2") (pintype "passive"))
      (node (ref "R9") (pin "1") (pinfunction "1_1") (pintype "passive"))
      (node (ref "R9") (pin "S1") (pinfunction "S_S1") (pintype "passive"))
      (node (ref "R9") (pin "S2") (pinfunction "S_S2") (pintype "passive"))
      (node (ref "U1") (pin "12") (pinfunction "GND_12") (pintype "passive"))
      (node (ref "U1") (pin "15") (pinfunction "~{E}_15") (pintype "input"))
      (node (ref "U2") (pin "12") (pinfunction "GND_12") (pintype "passive"))
      (node (ref "U2") (pin "15") (pinfunction "~{E}_15") (pintype "input"))
      (node (ref "U3") (pin "12") (pinfunction "GND_12") (pintype "passive"))
      (node (ref "U3") (pin "15") (pinfunction "~{E}_15") (pintype "input"))
      (node (ref "U4") (pin "12") (pinfunction "GND_12") (pintype "passive"))
      (node (ref "U4") (pin "15") (pinfunction "~{E}_15") (pintype "input"))
    )
    (net (code "3") (name "MUX_COMMON_1") (class "Default")
      (node (ref "CONN1") (pin "1") (pinfunction "1_1") (pintype "passive"))
      (node (ref "U1") (pin "1") (pinfunction "Z_1") (pintype "bidirectional"))
    )
    (net (code "4") (name "MUX_COMMON_2") (class "Default")
      (node (ref "CONN1") (pin "2") (pinfunction "2_2") (pintype "passive"))
      (node (ref "U2") (pin "1") (pinfunction "Z_1") (pintype "bidirectional"))
    )
    (net (code "5") (name "MUX_COMMON_3") (class "Default")
      (node (ref "CONN1") (pin "3") (pinfunction "3_3") (pintype "passive"))
      (node (ref "U3") (pin "1") (pinfunction "Z_1") (pintype "bidirectional"))
    )
    (net (code "6") (name "MUX_COMMON_4") (class "Default")
      (node (ref "CONN1") (pin "4") (pinfunction "4_4") (pintype "passive"))
      (node (ref "U4") (pin "1") (pinfunction "Z_1") (pintype "bidirectional"))
    )
    (net (code "7") (name "MUX_S0") (class "Default")
      (node (ref "CONN1") (pin "8") (pinfunction "8_8") (pintype "passive"))
      (node (ref "U1") (pin "10") (pinfunction "S0_10") (pintype "input"))
      (node (ref "U2") (pin "10") (pinfunction "S0_10") (pintype "input"))
      (node (ref "U3") (pin "10") (pinfunction "S0_10") (pintype "input"))
      (node (ref "U4") (pin "10") (pinfunction "S0_10") (pintype "input"))
    )
    (net (code "8") (name "MUX_S1") (class "Default")
      (node (ref "CONN1") (pin "7") (pinfunction "7_7") (pintype "passive"))
      (node (ref "U1") (pin "11") (pinfunction "S1_11") (pintype "input"))
      (node (ref "U2") (pin "11") (pinfunction "S1_11") (pintype "input"))
      (node (ref "U3") (pin "11") (pinfunction "S1_11") (pintype "input"))
      (node (ref "U4") (pin "11") (pinfunction "S1_11") (pintype "input"))
    )
    (net (code "9") (name "MUX_S2") (class "Default")
      (node (ref "CONN1") (pin "9") (pinfunction "9_9") (pintype "passive"))
      (node (ref "U1") (pin "14") (pinfunction "S2_14") (pintype "input"))
      (node (ref "U2") (pin "14") (pinfunction "S2_14") (pintype "input"))
      (node (ref "U3") (pin "14") (pinfunction "S2_14") (pintype "input"))
      (node (ref "U4") (pin "14") (pinfunction "S2_14") (pintype "input"))
    )
    (net (code "10") (name "MUX_S3") (class "Default")
      (node (ref "CONN1") (pin "10") (pinfunction "10_10") (pintype "passive"))
      (node (ref "U1") (pin "13") (pinfunction "S3_13") (pintype "input"))
      (node (ref "U2") (pin "13") (pinfunction "S3_13") (pintype "input"))
      (node (ref "U3") (pin "13") (pinfunction "S3_13") (pintype "input"))
      (node (ref "U4") (pin "13") (pinfunction "S3_13") (pintype "input"))
    )
    (net (code "11") (name "POT1") (class "Default")
      (node (ref "R1") (pin "2") (pinfunction "2_2") (pintype "passive"))
      (node (ref "U1") (pin "21") (pinfunction "Y10_21") (pintype "bidirectional"))
    )
    (net (code "12") (name "POT2") (class "Default")
      (node (ref "R2") (pin "2") (pinfunction "2_2") (pintype "passive"))
      (node (ref "U1") (pin "20") (pinfunction "Y11_20") (pintype "bidirectional"))
    )
    (net (code "13") (name "POT3") (class "Default")
      (node (ref "R3") (pin "2") (pinfunction "2_2") (pintype "passive"))
      (node (ref "U1") (pin "19") (pinfunction "Y12_19") (pintype "bidirectional"))
    )
    (net (code "14") (name "POT4") (class "Default")
      (node (ref "R4") (pin "2") (pinfunction "2_2") (pintype "passive"))
      (node (ref "U1") (pin "18") (pinfunction "Y13_18") (pintype "bidirectional"))
    )
    (net (code "15") (name "POT5") (class "Default")
      (node (ref "R5") (pin "2") (pinfunction "2_2") (pintype "passive"))
      (node (ref "U1") (pin "23") (pinfunction "Y8_23") (pintype "bidirectional"))
    )
    (net (code "16") (name "POT6") (class "Default")
      (node (ref "R6") (pin "2") (pinfunction "2_2") (pintype "passive"))
      (node (ref "U1") (pin "22") (pinfunction "Y9_22") (pintype "bidirectional"))
    )
    (net (code "17") (name "POT7") (class "Default")
      (node (ref "R7") (pin "2") (pinfunction "2_2") (pintype "passive"))
      (node (ref "U1") (pin "17") (pinfunction "Y14_17") (pintype "bidirectional"))
    )
    (net (code "18") (name "POT8") (class "Default")
      (node (ref "R8") (pin "2") (pinfunction "2_2") (pintype "passive"))
      (node (ref "U1") (pin "16") (pinfunction "Y15_16") (pintype "bidirectional"))
    )
    (net (code "19") (name "POT9") (class "Default")
      (node (ref "R9") (pin "2") (pinfunction "2_2") (pintype "passive"))
      (node (ref "U1") (pin "2") (pinfunction "Y7_2") (pintype "bidirectional"))
    )
    (net (code "20") (name "POT10") (class "Default")
      (node (ref "R10") (pin "2") (pinfunction "2_2") (pintype "passive"))
      (node (ref "U1") (pin "3") (pinfunction "Y6_3") (pintype "bidirectional"))
    )
    (net (code "21") (name "POT11") (class "Default")
      (node (ref "R11") (pin "2") (pinfunction "2_2") (pintype "passive"))
      (node (ref "U1") (pin "8") (pinfunction "Y1_8") (pintype "bidirectional"))
    )
    (net (code "22") (name "POT12") (class "Default")
      (node (ref "R12") (pin "2") (pinfunction "2_2") (pintype "passive"))
      (node (ref "U1") (pin "9") (pinfunction "Y0_9") (pintype "bidirectional"))
    )
    (net (code "23") (name "POT13") (class "Default")
      (node (ref "R13") (pin "2") (pinfunction "2_2") (pintype "passive"))
      (node (ref "U1") (pin "4") (pinfunction "Y5_4") (pintype "bidirectional"))
    )
    (net (code "24") (name "POT14") (class "Default")
      (node (ref "R14") (pin "2") (pinfunction "2_2") (pintype "passive"))
      (node (ref "U1") (pin "5") (pinfunction "Y4_5") (pintype "bidirectional"))
    )
    (net (code "25") (name "POT15") (class "Default")
      (node (ref "R15") (pin "2") (pinfunction "2_2") (pintype "passive"))
      (node (ref "U1") (pin "6") (pinfunction "Y3_6") (pintype "bidirectional"))
    )
    (net (code "26") (name "POT16") (class "Default")
      (node (ref "R16") (pin "2") (pinfunction "2_2") (pintype "passive"))
      (node (ref "U1") (pin "7") (pinfunction "Y2_7") (pintype "bidirectional"))
    )
    (net (code "27") (name "POT17") (class "Default")
      (node (ref "R17") (pin "2") (pinfunction "2_2") (pintype "passive"))
      (node (ref "U2") (pin "21") (pinfunction "Y10_21") (pintype "bidirectional"))
    )
    (net (code "28") (name "POT18") (class "Default")
      (node (ref "R18") (pin "2") (pinfunction "2_2") (pintype "passive"))
      (node (ref "U2") (pin "20") (pinfunction "Y11_20") (pintype "bidirectional"))
    )
    (net (code "29") (name "POT19") (class "Default")
      (node (ref "R19") (pin "2") (pinfunction "2_2") (pintype "passive"))
      (node (ref "U2") (pin "19") (pinfunction "Y12_19") (pintype "bidirectional"))
    )
    (net (code "30") (name "POT20") (class "Default")
      (node (ref "R20") (pin "2") (pinfunction "2_2") (pintype "passive"))
      (node (ref "U2") (pin "18") (pinfunction "Y13_18") (pintype "bidirectional"))
    )
    (net (code "31") (name "POT21") (class "Default")
      (node (ref "R21") (pin "2") (pinfunction "2_2") (pintype "passive"))
      (node (ref "U2") (pin "23") (pinfunction "Y8_23") (pintype "bidirectional"))
    )
    (net (code "32") (name "POT22") (class "Default")
      (node (ref "R22") (pin "2") (pinfunction "2_2") (pintype "passive"))
      (node (ref "U2") (pin "22") (pinfunction "Y9_22") (pintype "bidirectional"))
    )
    (net (code "33") (name "POT23") (class "Default")
      (node (ref "R23") (pin "2") (pinfunction "2_2") (pintype "passive"))
      (node (ref "U2") (pin "17") (pinfunction "Y14_17") (pintype "bidirectional"))
    )
    (net (code "34") (name "POT24") (class "Default")
      (node (ref "R24") (pin "2") (pinfunction "2_2") (pintype "passive"))
      (node (ref "U2") (pin "16") (pinfunction "Y15_16") (pintype "bidirectional"))
    )
    (net (code "35") (name "POT25") (class "Default")
      (node (ref "R25") (pin "2") (pinfunction "2_2") (pintype "passive"))
      (node (ref "U2") (pin "2") (pinfunction "Y7_2") (pintype "bidirectional"))
    )
    (net (code "36") (name "POT26") (class "Default")
      (node (ref "R26") (pin "2") (pinfunction "2_2") (pintype "passive"))
      (node (ref "U2") (pin "3") (pinfunction "Y6_3") (pintype "bidirectional"))
    )
    (net (code "37") (name "POT27") (class "Default")
      (node (ref "R27") (pin "2") (pinfunction "2_2") (pintype "passive"))
      (node (ref "U2") (pin "8") (pinfunction "Y1_8") (pintype "bidirectional"))
    )
    (net (code "38") (name "POT28") (class "Default")
      (node (ref "R28") (pin "2") (pinfunction "2_2") (pintype "passive"))
      (node (ref "U2") (pin "9") (pinfunction "Y0_9") (pintype "bidirectional"))
    )
    (net (code "39") (name "POT29") (class "Default")
      (node (ref "R29") (pin "2") (pinfunction "2_2") (pintype "passive"))
      (node (ref "U2") (pin "4") (pinfunction "Y5_4") (pintype "bidirectional"))
    )
    (net (code "40") (name "POT30") (class "Default")
      (node (ref "R30") (pin "2") (pinfunction "2_2") (pintype "passive"))
      (node (ref "U2") (pin "5") (pinfunction "Y4_5") (pintype "bidirectional"))
    )
    (net (code "41") (name "POT31") (class "Default")
      (node (ref "R31") (pin "2") (pinfunction "2_2") (pintype "passive"))
      (node (ref "U2") (pin "6") (pinfunction "Y3_6") (pintype "bidirectional"))
    )
    (net (code "42") (name "POT32") (class "Default")
      (node (ref "R32") (pin "2") (pinfunction "2_2") (pintype "passive"))
      (node (ref "U2") (pin "7") (pinfunction "Y2_7") (pintype "bidirectional"))
    )
    (net (code "43") (name "POT33") (class "Default")
      (node (ref "R33") (pin "2") (pinfunction "2_2") (pintype "passive"))
      (node (ref "U3") (pin "21") (pinfunction "Y10_21") (pintype "bidirectional"))
    )
    (net (code "44") (name "POT34") (class "Default")
      (node (ref "R34") (pin "2") (pinfunction "2_2") (pintype "passive"))
      (node (ref "U3") (pin "20") (pinfunction "Y11_20") (pintype "bidirectional"))
    )
    (net (code "45") (name "POT35") (class "Default")
      (node (ref "R35") (pin "2") (pinfunction "2_2") (pintype "passive"))
      (node (ref "U3") (pin "19") (pinfunction "Y12_19") (pintype "bidirectional"))
    )
    (net (code "46") (name "POT36") (class "Default")
      (node (ref "R36") (pin "2") (pinfunction "2_2") (pintype "passive"))
      (node (ref "U3") (pin "18") (pinfunction "Y13_18") (pintype "bidirectional"))
    )
    (net (code "47") (name "POT37") (class "Default")
      (node (ref "R37") (pin "2") (pinfunction "2_2") (pintype "passive"))
      (node (ref "U3") (pin "23") (pinfunction "Y8_23") (pintype "bidirectional"))
    )
    (net (code "48") (name "POT38") (class "Default")
      (node (ref "R38") (pin "2") (pinfunction "2_2") (pintype "passive"))
      (node (ref "U3") (pin "22") (pinfunction "Y9_22") (pintype "bidirectional"))
    )
    (net (code "49") (name "POT39") (class "Default")
      (node (ref "R39") (pin "2") (pinfunction "2_2") (pintype "passive"))
      (node (ref "U3") (pin "17") (pinfunction "Y14_17") (pintype "bidirectional"))
    )
    (net (code "50") (name "POT40") (class "Default")
      (node (ref "R40") (pin "2") (pinfunction "2_2") (pintype "passive"))
      (node (ref "U3") (pin "16") (pinfunction "Y15_16") (pintype "bidirectional"))
    )
    (net (code "51") (name "POT41") (class "Default")
      (node (ref "R41") (pin "2") (pinfunction "2_2") (pintype "passive"))
      (node (ref "U3") (pin "2") (pinfunction "Y7_2") (pintype "bidirectional"))
    )
    (net (code "52") (name "POT42") (class "Default")
      (node (ref "R42") (pin "2") (pinfunction "2_2") (pintype "passive"))
      (node (ref "U3") (pin "3") (pinfunction "Y6_3") (pintype "bidirectional"))
    )
    (net (code "53") (name "POT43") (class "Default")
      (node (ref "R43") (pin "2") (pinfunction "2_2") (pintype "passive"))
      (node (ref "U3") (pin "8") (pinfunction "Y1_8") (pintype "bidirectional"))
    )
    (net (code "54") (name "POT44") (class "Default")
      (node (ref "R44") (pin "2") (pinfunction "2_2") (pintype "passive"))
      (node (ref "U3") (pin "9") (pinfunction "Y0_9") (pintype "bidirectional"))
    )
    (net (code "55") (name "POT45") (class "Default")
      (node (ref "R45") (pin "2") (pinfunction "2_2") (pintype "passive"))
      (node (ref "U3") (pin "4") (pinfunction "Y5_4") (pintype "bidirectional"))
    )
    (net (code "56") (name "POT46") (class "Default")
      (node (ref "R46") (pin "2") (pinfunction "2_2") (pintype "passive"))
      (node (ref "U3") (pin "5") (pinfunction "Y4_5") (pintype "bidirectional"))
    )
    (net (code "57") (name "POT47") (class "Default")
      (node (ref "R47") (pin "2") (pinfunction "2_2") (pintype "passive"))
      (node (ref "U3") (pin "6") (pinfunction "Y3_6") (pintype "bidirectional"))
    )
    (net (code "58") (name "POT48") (class "Default")
      (node (ref "R48") (pin "2") (pinfunction "2_2") (pintype "passive"))
      (node (ref "U3") (pin "7") (pinfunction "Y2_7") (pintype "bidirectional"))
    )
    (net (code "59") (name "POT49") (class "Default")
      (node (ref "R49") (pin "2") (pinfunction "2_2") (pintype "passive"))
      (node (ref "U4") (pin "21") (pinfunction "Y10_21") (pintype "bidirectional"))
    )
    (net (code "60") (name "POT50") (class "Default")
      (node (ref "R50") (pin "2") (pinfunction "2_2") (pintype "passive"))
      (node (ref "U4") (pin "20") (pinfunction "Y11_20") (pintype "bidirectional"))
    )
    (net (code "61") (name "POT51") (class "Default")
      (node (ref "R51") (pin "2") (pinfunction "2_2") (pintype "passive"))
      (node (ref "U4") (pin "19") (pinfunction "Y12_19") (pintype "bidirectional"))
    )
    (net (code "62") (name "POT52") (class "Default")
      (node (ref "R52") (pin "2") (pinfunction "2_2") (pintype "passive"))
      (node (ref "U4") (pin "18") (pinfunction "Y13_18") (pintype "bidirectional"))
    )
    (net (code "63") (name "POT53") (class "Default")
      (node (ref "R53") (pin "2") (pinfunction "2_2") (pintype "passive"))
      (node (ref "U4") (pin "23") (pinfunction "Y8_23") (pintype "bidirectional"))
    )
    (net (code "64") (name "POT54") (class "Default")
      (node (ref "R54") (pin "2") (pinfunction "2_2") (pintype "passive"))
      (node (ref "U4") (pin "22") (pinfunction "Y9_22") (pintype "bidirectional"))
    )
    (net (code "65") (name "POT55") (class "Default")
      (node (ref "R55") (pin "2") (pinfunction "2_2") (pintype "passive"))
      (node (ref "U4") (pin "17") (pinfunction "Y14_17") (pintype "bidirectional"))
    )
    (net (code "66") (name "POT56") (class "Default")
      (node (ref "R56") (pin "2") (pinfunction "2_2") (pintype "passive"))
      (node (ref "U4") (pin "16") (pinfunction "Y15_16") (pintype "bidirectional"))
    )
    (net (code "67") (name "POT57") (class "Default")
      (node (ref "R57") (pin "2") (pinfunction "2_2") (pintype "passive"))
      (node (ref "U4") (pin "2") (pinfunction "Y7_2") (pintype "bidirectional"))
    )
    (net (code "68") (name "POT58") (class "Default")
      (node (ref "R58") (pin "2") (pinfunction "2_2") (pintype "passive"))
      (node (ref "U4") (pin "3") (pinfunction "Y6_3") (pintype "bidirectional"))
    )
    (net (code "69") (name "POT59") (class "Default")
      (node (ref "R59") (pin "2") (pinfunction "2_2") (pintype "passive"))
      (node (ref "U4") (pin "8") (pinfunction "Y1_8") (pintype "bidirectional"))
    )
    (net (code "70") (name "POT60") (class "Default")
      (node (ref "R60") (pin "2") (pinfunction "2_2") (pintype "passive"))
      (node (ref "U4") (pin "9") (pinfunction "Y0_9") (pintype "bidirectional"))
    )
    (net (code "71") (name "POT61") (class "Default")
      (node (ref "R61") (pin "2") (pinfunction "2_2") (pintype "passive"))
      (node (ref "U4") (pin "4") (pinfunction "Y5_4") (pintype "bidirectional"))
    )
    (net (code "72") (name "POT62") (class "Default")
      (node (ref "R62") (pin "2") (pinfunction "2_2") (pintype "passive"))
      (node (ref "U4") (pin "5") (pinfunction "Y4_5") (pintype "bidirectional"))
    )
    (net (code "73") (name "POT63") (class "Default")
      (node (ref "R63") (pin "2") (pinfunction "2_2") (pintype "passive"))
      (node (ref "U4") (pin "6") (pinfunction "Y3_6") (pintype "bidirectional"))
    )
    (net (code "74") (name "POT64") (class "Default")
      (node (ref "R64") (pin "2") (pinfunction "2_2") (pintype "passive"))
      (node (ref "U4") (pin "7") (pinfunction "Y2_7") (pintype "bidirectional"))
    )
  )
)
